# MAIN.net
KiCad netlist of a schematic drawn in Altium Designer
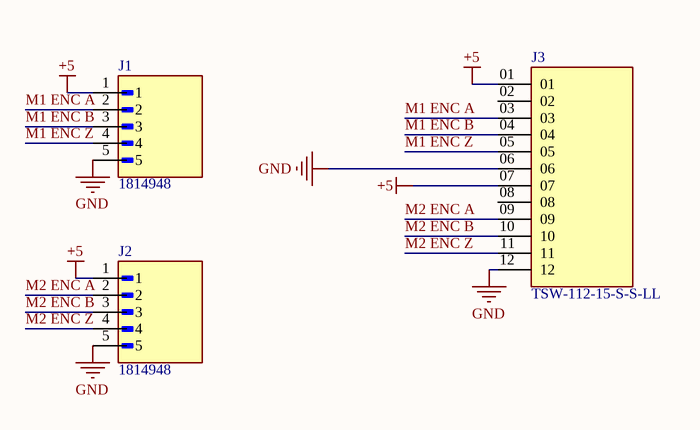
[diagram p0: MAIN.SchDoc]

(export (version "E")
  (design (tool "Eeschema 10.0.6"))
  (components
    (comp (ref "J1")
      (value "1814948")
      (footprint "PHOENIX_1814948")
      (libsource (lib "rover_electronics") (part "1814948"))
    )
    (comp (ref "J2")
      (value "1814948")
      (footprint "PHOENIX_1814948")
      (libsource (lib "rover_electronics") (part "1814948"))
    )
    (comp (ref "J3")
      (value "TSW-112-15-S-S-LL")
      (footprint "SAMTEC_TSW-112-15-S-S-LL")
      (libsource (lib "rover_electronics") (part "TSW-112-15-S-S-LL"))
    )
  )
  (nets
    (net (code "1") (name "+5") (class "Default")
      (node (ref "J1") (pin "1") (pinfunction "1_1") (pintype "passive"))
      (node (ref "J2") (pin "1") (pinfunction "1_1") (pintype "passive"))
      (node (ref "J3") (pin "01") (pinfunction "01_01") (pintype "passive"))
      (node (ref "J3") (pin "07") (pinfunction "07_07") (pintype "passive"))
    )
    (net (code "2") (name "/M1 ENC A") (class "Default")
      (node (ref "J1") (pin "2") (pinfunction "2_2") (pintype "passive"))
      (node (ref "J3") (pin "03") (pinfunction "03_03") (pintype "passive"))
    )
    (net (code "3") (name "/M1 ENC B") (class "Default")
      (node (ref "J1") (pin "3") (pinfunction "3_3") (pintype "passive"))
      (node (ref "J3") (pin "04") (pinfunction "04_04") (pintype "passive"))
    )
    (net (code "4") (name "/M1 ENC Z") (class "Default")
      (node (ref "J1") (pin "4") (pinfunction "4_4") (pintype "passive"))
      (node (ref "J3") (pin "05") (pinfunction "05_05") (pintype "passive"))
    )
    (net (code "5") (name "/M2 ENC A") (class "Default")
      (node (ref "J2") (pin "2") (pinfunction "2_2") (pintype "passive"))
      (node (ref "J3") (pin "09") (pinfunction "09_09") (pintype "passive"))
    )
    (net (code "6") (name "/M2 ENC B") (class "Default")
      (node (ref "J2") (pin "3") (pinfunction "3_3") (pintype "passive"))
      (node (ref "J3") (pin "10") (pinfunction "10_10") (pintype "passive"))
    )
    (net (code "7") (name "/M2 ENC Z") (class "Default")
      (node (ref "J2") (pin "4") (pinfunction "4_4") (pintype "passive"))
      (node (ref "J3") (pin "11") (pinfunction "11_11") (pintype "passive"))
    )
    (net (code "8") (name "GND") (class "Default")
      (node (ref "J1") (pin "5") (pinfunction "5_5") (pintype "passive"))
      (node (ref "J2") (pin "5") (pinfunction "5_5") (pintype "passive"))
      (node (ref "J3") (pin "06") (pinfunction "06_06") (pintype "passive"))
      (node (ref "J3") (pin "12") (pinfunction "12_12") (pintype "passive"))
    )
    (net (code "9") (name "unconnected-(J3-Pad02)") (class "Default")
      (node (ref "J3") (pin "02") (pinfunction "02_02") (pintype "passive"))
    )
    (net (code "10") (name "unconnected-(J3-Pad08)") (class "Default")
      (node (ref "J3") (pin "08") (pinfunction "08_08") (pintype "passive"))
    )
  )
)
